# NEURON_EASYEDA.net
KiCad netlist of a schematic drawn in EasyEDA
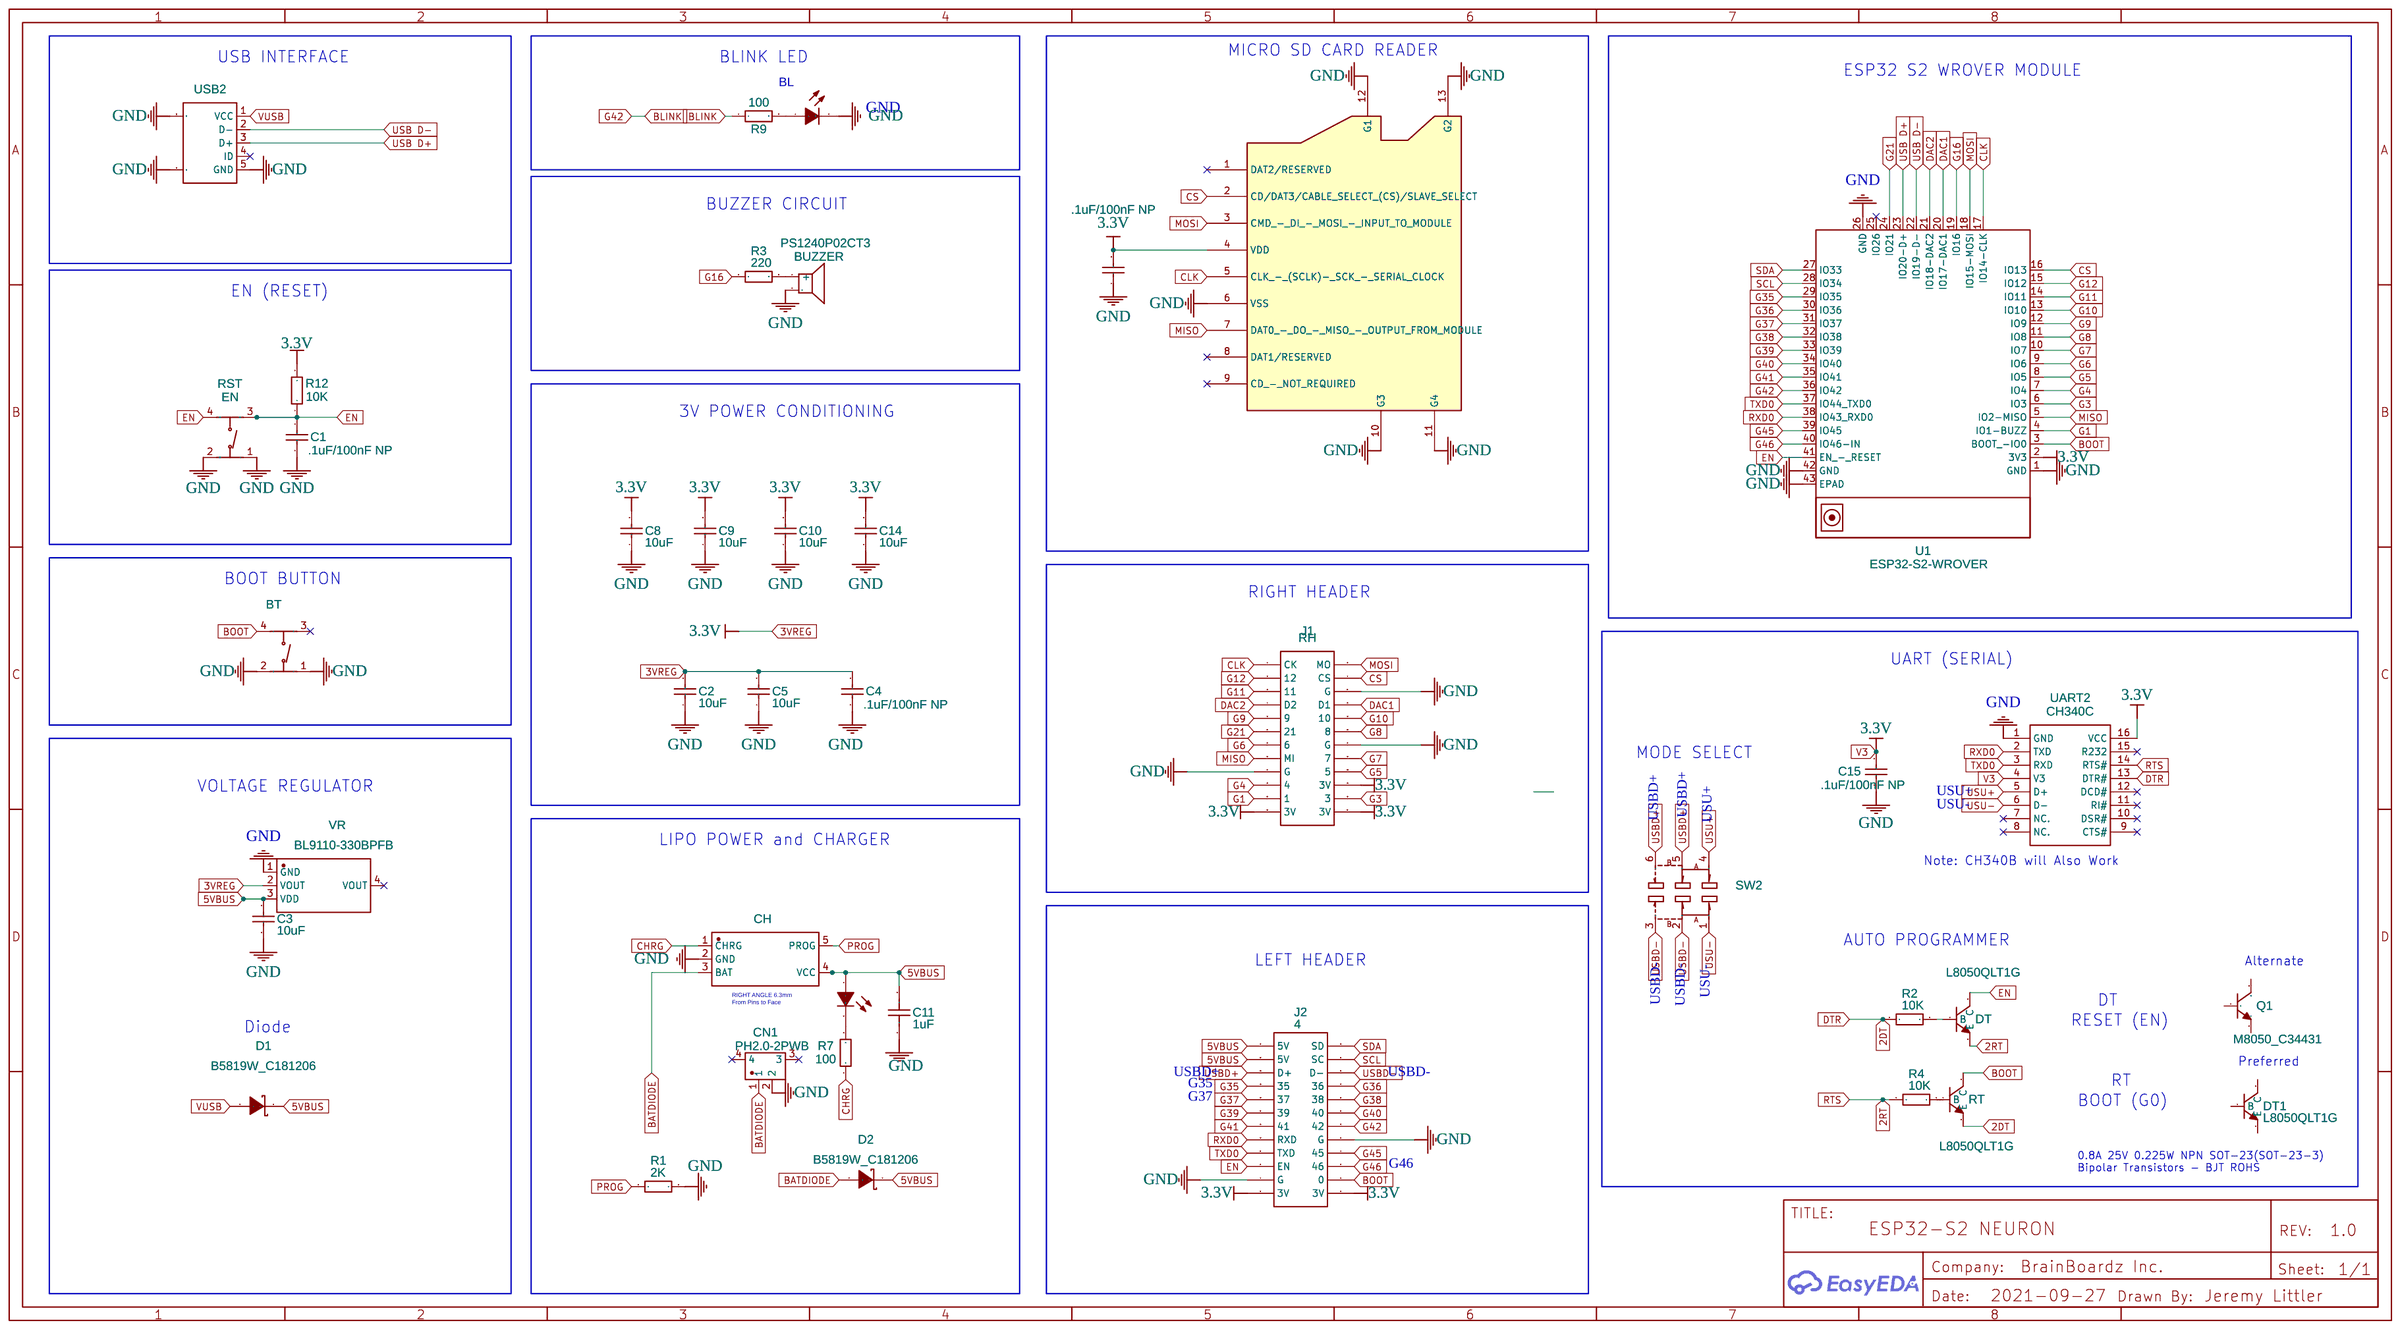
[diagram p0: schematic sheet]

(export (version "E")
  (design (tool "Eeschema 10.0.6"))
  (components
    (comp (ref "BLINK")
      (value "15-21SYGC/S530-E2/TR8")
      (fields (field (name "BOM_Supplier Part") "C73550"))
      (libsource (lib "") (part "15-21SYGC/S530-E2/TR8_1"))
    )
    (comp (ref "BT")
      (value "BOOT")
      (fields
        (field (name "BOM_Manufacturer Part") "TS-1187A-C-E-B")
        (field (name "BOM_Supplier Part") "C318887")
      )
      (libsource (lib "") (part "TS-1187A-C-E-B"))
    )
    (comp (ref "BUZZER")
      (value "PS1240P02CT3")
      (fields (field (name "BOM_Supplier Part") "C76873"))
      (libsource (lib "") (part "PS1240P02CT3"))
    )
    (comp (ref "C1")
      (value ".1uF/100nF NP")
      (fields
        (field (name "BOM_Manufacturer Part") "CL31B104KBCNNNC")
        (field (name "BOM_Supplier Part") "C24497")
      )
      (libsource (lib "") (part "CL31B104KBCNNNC_1"))
    )
    (comp (ref "C2")
      (value "10uF")
      (fields
        (field (name "BOM_Manufacturer Part") "CL31A106KBHNNNE")
        (field (name "BOM_Supplier Part") "C13585")
      )
      (libsource (lib "") (part "CL31A106KBHNNNE"))
    )
    (comp (ref "C3")
      (value "10uF")
      (fields
        (field (name "BOM_Manufacturer Part") "CL31A106KBHNNNE")
        (field (name "BOM_Supplier Part") "C13585")
      )
      (libsource (lib "") (part "CL31A106KBHNNNE"))
    )
    (comp (ref "C4")
      (value ".1uF/100nF NP")
      (fields
        (field (name "BOM_Manufacturer Part") "CL31B104KBCNNNC")
        (field (name "BOM_Supplier Part") "C24497")
      )
      (libsource (lib "") (part "CL31B104KBCNNNC_1"))
    )
    (comp (ref "C5")
      (value "10uF")
      (fields
        (field (name "BOM_Manufacturer Part") "CL31A106KBHNNNE")
        (field (name "BOM_Supplier Part") "C13585")
      )
      (libsource (lib "") (part "CL31A106KBHNNNE"))
    )
    (comp (ref "C8")
      (value "10uF")
      (fields
        (field (name "BOM_Manufacturer Part") "CL31A106KBHNNNE")
        (field (name "BOM_Supplier Part") "C13585")
      )
      (libsource (lib "") (part "CL31A106KBHNNNE"))
    )
    (comp (ref "C9")
      (value "10uF")
      (fields
        (field (name "BOM_Manufacturer Part") "CL31A106KBHNNNE")
        (field (name "BOM_Supplier Part") "C13585")
      )
      (libsource (lib "") (part "CL31A106KBHNNNE"))
    )
    (comp (ref "C10")
      (value "10uF")
      (fields
        (field (name "BOM_Manufacturer Part") "CL31A106KBHNNNE")
        (field (name "BOM_Supplier Part") "C13585")
      )
      (libsource (lib "") (part "CL31A106KBHNNNE"))
    )
    (comp (ref "C11")
      (value "1uF")
      (fields
        (field (name "BOM_Manufacturer Part") "CL31B105KBHNNNE")
        (field (name "BOM_Supplier Part") "C1848")
      )
      (libsource (lib "") (part "CL31B105KBHNNNE"))
    )
    (comp (ref "C13")
      (value ".1uF/100nF NP")
      (fields
        (field (name "BOM_Manufacturer Part") "CL31B104KBCNNNC")
        (field (name "BOM_Supplier Part") "C24497")
      )
      (libsource (lib "") (part "CL31B104KBCNNNC"))
    )
    (comp (ref "C14")
      (value "10uF")
      (fields
        (field (name "BOM_Manufacturer Part") "CL31A106KBHNNNE")
        (field (name "BOM_Supplier Part") "C13585")
      )
      (libsource (lib "") (part "CL31A106KBHNNNE"))
    )
    (comp (ref "C15")
      (value ".1uF/100nF NP")
      (fields
        (field (name "BOM_Manufacturer Part") "CL31B104KBCNNNC")
        (field (name "BOM_Supplier Part") "C24497")
      )
      (libsource (lib "") (part "CL31B104KBCNNNC"))
    )
    (comp (ref "CG")
      (value "15-21SYGC/S530-E2/TR8")
      (fields (field (name "BOM_Supplier Part") "C73550"))
      (libsource (lib "") (part "15-21SYGC/S530-E2/TR8"))
    )
    (comp (ref "CH")
      (value "CH")
      (fields (field (name "BOM_Manufacturer Part") "TP4054") (field (name "BOM_Supplier Part") "C32574"))
      (libsource (lib "") (part "TP4054"))
    )
    (comp (ref "CN1")
      (value "PH2.0-2PWB")
      (fields
        (field (name "BOM_Manufacturer Part") "PH2.0-2PWB Horizontal")
        (field (name "BOM_Supplier Part") "C47647")
      )
      (libsource (lib "") (part "PH2.0-2PWB"))
    )
    (comp (ref "D1")
      (value "B5819W_C181206")
      (fields (field (name "BOM_Manufacturer Part") "B5819W") (field (name "BOM_Supplier Part") "C181206"))
      (libsource (lib "") (part "B5819W_C181206"))
    )
    (comp (ref "D2")
      (value "B5819W_C181206")
      (fields (field (name "BOM_Manufacturer Part") "B5819W") (field (name "BOM_Supplier Part") "C181206"))
      (libsource (lib "") (part "B5819W_C181206"))
    )
    (comp (ref "DT")
      (value "L8050QLT1G")
      (fields (field (name "BOM_Supplier Part") "C49581"))
      (libsource (lib "") (part "L8050QLT1G"))
    )
    (comp (ref "DT1")
      (value "L8050QLT1G")
      (fields (field (name "BOM_Supplier Part") "C49581"))
      (libsource (lib "") (part "L8050QLT1G"))
    )
    (comp (ref "J1")
      (value "RH")
      (fields (field (name "BOM_Manufacturer Part") "New SchematicLib"))
      (libsource (lib "") (part "HDR 2.54mm 2x12_1"))
    )
    (comp (ref "J2")
      (value "4")
      (fields (field (name "BOM_Manufacturer Part") "New SchematicLib"))
      (libsource (lib "") (part "HDR 2.54mm 2x12"))
    )
    (comp (ref "MICROSD")
      (value "TF-15×15")
      (fields (field (name "BOM_Supplier Part") "C111196"))
      (libsource (lib "") (part "TF-15×15"))
    )
    (comp (ref "Q1")
      (value "M8050_C34431")
      (fields (field (name "BOM_Manufacturer Part") "M8050") (field (name "BOM_Supplier Part") "C34431"))
      (libsource (lib "") (part "M8050_C34431"))
    )
    (comp (ref "R1")
      (value "2K")
      (fields
        (field (name "BOM_Manufacturer Part") "1206W4F2001T5E")
        (field (name "BOM_Supplier Part") "C17944")
      )
      (libsource (lib "") (part "1206W4F2001T5E"))
    )
    (comp (ref "R2")
      (value "10K")
      (fields
        (field (name "BOM_Manufacturer Part") "AECR1206F10K0K9")
        (field (name "BOM_Supplier Part") "C328409")
      )
      (libsource (lib "") (part "AECR1206F10K0K9_1"))
    )
    (comp (ref "R3")
      (value "220")
      (fields
        (field (name "BOM_Manufacturer Part") "1206W4J0221T5E")
        (field (name "BOM_Supplier Part") "C25363")
      )
      (libsource (lib "") (part "1206W4J0221T5E"))
    )
    (comp (ref "R4")
      (value "10K")
      (fields
        (field (name "BOM_Manufacturer Part") "AECR1206F10K0K9")
        (field (name "BOM_Supplier Part") "C328409")
      )
      (libsource (lib "") (part "AECR1206F10K0K9_1"))
    )
    (comp (ref "R7")
      (value "100")
      (fields
        (field (name "BOM_Manufacturer Part") "1206W4F1000T5E")
        (field (name "BOM_Supplier Part") "C17901")
      )
      (libsource (lib "") (part "1206W4F1000T5E"))
    )
    (comp (ref "R9")
      (value "100")
      (fields
        (field (name "BOM_Manufacturer Part") "1206W4F1000T5E")
        (field (name "BOM_Supplier Part") "C17901")
      )
      (libsource (lib "") (part "1206W4F1000T5E_1"))
    )
    (comp (ref "R12")
      (value "10K")
      (fields
        (field (name "BOM_Manufacturer Part") "AECR1206F10K0K9")
        (field (name "BOM_Supplier Part") "C328409")
      )
      (libsource (lib "") (part "AECR1206F10K0K9"))
    )
    (comp (ref "RST")
      (value "EN")
      (fields
        (field (name "BOM_Manufacturer Part") "TS-1187A-C-E-B")
        (field (name "BOM_Supplier Part") "C318887")
      )
      (libsource (lib "") (part "TS-1187A-C-E-B_1"))
    )
    (comp (ref "RT")
      (value "L8050QLT1G")
      (fields (field (name "BOM_Supplier Part") "C49581"))
      (libsource (lib "") (part "L8050QLT1G_1"))
    )
    (comp (ref "SW2")
      (value "K2-2235D-F1")
      (fields (field (name "BOM_Supplier Part") "C108742"))
      (libsource (lib "") (part "K2-2235D-F1"))
    )
    (comp (ref "U1")
      (value "ESP32-S2-WROVER")
      (fields (field (name "BOM_Manufacturer Part") "ESP32-S2-WROVER-I"))
      (libsource (lib "") (part "ESP32-S2-WROVER-I"))
    )
    (comp (ref "UART2")
      (value "CH340C")
      (fields (field (name "BOM_Supplier Part") "C84681"))
      (libsource (lib "") (part "CH340C"))
    )
    (comp (ref "USB2")
      (value "Mini USB-B 5P-Female-TH_C46398")
      (fields
        (field (name "BOM_Manufacturer Part") "MINI 5PFemale90Degree plate four feet copper shell LCPVinyl")
        (field (name "BOM_Supplier Part") "C46398")
      )
      (libsource (lib "") (part "Mini USB-B 5P-Female-TH_C46398"))
    )
    (comp (ref "VR")
      (value "BL9110-330BPFB")
      (fields (field (name "BOM_Supplier Part") "C169246"))
      (libsource (lib "") (part "BL9110-330BPFB"))
    )
  )
  (nets
    (net (code "1") (name "2DT") (class "Default")
      (node (ref "R2") (pin "2") (pinfunction "2_2") (pintype "unspecified"))
      (node (ref "RT") (pin "2") (pinfunction "E_2") (pintype "unspecified"))
      (node (ref "UART2") (pin "13") (pinfunction "DTR#_13") (pintype "unspecified"))
    )
    (net (code "2") (name "2RT") (class "Default")
      (node (ref "DT") (pin "2") (pinfunction "E_2") (pintype "unspecified"))
      (node (ref "R4") (pin "2") (pinfunction "2_2") (pintype "unspecified"))
      (node (ref "UART2") (pin "14") (pinfunction "RTS#_14") (pintype "unspecified"))
    )
    (net (code "3") (name "3VREG") (class "Default")
      (node (ref "C10") (pin "2") (pinfunction "2_2") (pintype "input"))
      (node (ref "C13") (pin "2") (pinfunction "2_2") (pintype "input"))
      (node (ref "C14") (pin "2") (pinfunction "2_2") (pintype "input"))
      (node (ref "C15") (pin "2") (pinfunction "2_2") (pintype "input"))
      (node (ref "C2") (pin "2") (pinfunction "2_2") (pintype "input"))
      (node (ref "C4") (pin "1") (pinfunction "1_1") (pintype "input"))
      (node (ref "C5") (pin "2") (pinfunction "2_2") (pintype "input"))
      (node (ref "C8") (pin "2") (pinfunction "2_2") (pintype "input"))
      (node (ref "C9") (pin "2") (pinfunction "2_2") (pintype "input"))
      (node (ref "J1") (pin "20") (pinfunction "3V_20") (pintype "unspecified"))
      (node (ref "J1") (pin "23") (pinfunction "3V_23") (pintype "unspecified"))
      (node (ref "J1") (pin "24") (pinfunction "3V_24") (pintype "unspecified"))
      (node (ref "J2") (pin "1") (pinfunction "3V_1") (pintype "unspecified"))
      (node (ref "J2") (pin "2") (pinfunction "3V_2") (pintype "unspecified"))
      (node (ref "MICROSD") (pin "4") (pinfunction "VDD_4") (pintype "input"))
      (node (ref "R12") (pin "2") (pinfunction "2_2") (pintype "unspecified"))
      (node (ref "U1") (pin "2") (pinfunction "3V3_2") (pintype "unspecified"))
      (node (ref "UART2") (pin "16") (pinfunction "VCC_16") (pintype "unspecified"))
      (node (ref "UART2") (pin "4") (pinfunction "V3_4") (pintype "unspecified"))
      (node (ref "VR") (pin "2") (pinfunction "VOUT_2") (pintype "unspecified"))
    )
    (net (code "4") (name "5VBUS") (class "Default")
      (node (ref "C11") (pin "2") (pinfunction "2_2") (pintype "unspecified"))
      (node (ref "C3") (pin "2") (pinfunction "2_2") (pintype "input"))
      (node (ref "CG") (pin "1") (pinfunction "A_1") (pintype "input"))
      (node (ref "CH") (pin "4") (pinfunction "VCC_4") (pintype "unspecified"))
      (node (ref "D1") (pin "1") (pinfunction "K_1") (pintype "unspecified"))
      (node (ref "D2") (pin "1") (pinfunction "K_1") (pintype "unspecified"))
      (node (ref "J2") (pin "22") (pinfunction "5V_22") (pintype "unspecified"))
      (node (ref "J2") (pin "24") (pinfunction "5V_24") (pintype "unspecified"))
      (node (ref "VR") (pin "3") (pinfunction "VDD_3") (pintype "unspecified"))
    )
    (net (code "5") (name "BATDIODE") (class "Default")
      (node (ref "CH") (pin "3") (pinfunction "BAT_3") (pintype "unspecified"))
      (node (ref "CN1") (pin "1") (pinfunction "1_1") (pintype "unspecified"))
      (node (ref "D2") (pin "2") (pinfunction "A_2") (pintype "unspecified"))
    )
    (net (code "6") (name "BLINK") (class "Default")
      (node (ref "J2") (pin "11") (pinfunction "42_11") (pintype "unspecified"))
      (node (ref "R9") (pin "1") (pinfunction "1_1") (pintype "input"))
      (node (ref "U1") (pin "36") (pinfunction "IO42_36") (pintype "unspecified"))
    )
    (net (code "7") (name "BOOT") (class "Default")
      (node (ref "BT") (pin "4") (pinfunction "D_4") (pintype "unspecified"))
      (node (ref "J2") (pin "3") (pinfunction "0_3") (pintype "unspecified"))
      (node (ref "RT") (pin "3") (pinfunction "C_3") (pintype "unspecified"))
      (node (ref "U1") (pin "3") (pinfunction "BOOT_-IO0_3") (pintype "unspecified"))
    )
    (net (code "8") (name "CHRG") (class "Default")
      (node (ref "CH") (pin "1") (pinfunction "CHRG_1") (pintype "unspecified"))
      (node (ref "R7") (pin "1") (pinfunction "1_1") (pintype "input"))
    )
    (net (code "9") (name "CLK") (class "Default")
      (node (ref "J1") (pin "1") (pinfunction "CK_1") (pintype "unspecified"))
      (node (ref "MICROSD") (pin "5") (pinfunction "CLK_-_(SCLK)-_SCK_-_SERIAL_CLOCK_5") (pintype "input"))
      (node (ref "U1") (pin "17") (pinfunction "IO14-CLK_17") (pintype "unspecified"))
    )
    (net (code "10") (name "CS") (class "Default")
      (node (ref "J1") (pin "4") (pinfunction "CS_4") (pintype "unspecified"))
      (node (ref "MICROSD") (pin "2") (pinfunction "CD/DAT3/CABLE_SELECT_(CS)/SLAVE_SELECT_2") (pintype "input"))
      (node (ref "U1") (pin "16") (pinfunction "IO13_16") (pintype "unspecified"))
    )
    (net (code "11") (name "DAC1") (class "Default")
      (node (ref "J1") (pin "8") (pinfunction "D1_8") (pintype "unspecified"))
      (node (ref "U1") (pin "20") (pinfunction "IO17-DAC1_20") (pintype "unspecified"))
    )
    (net (code "12") (name "DAC2") (class "Default")
      (node (ref "J1") (pin "7") (pinfunction "D2_7") (pintype "unspecified"))
      (node (ref "U1") (pin "21") (pinfunction "IO18-DAC2_21") (pintype "unspecified"))
    )
    (net (code "13") (name "EN") (class "Default")
      (node (ref "C1") (pin "1") (pinfunction "1_1") (pintype "input"))
      (node (ref "DT") (pin "3") (pinfunction "C_3") (pintype "unspecified"))
      (node (ref "J2") (pin "6") (pinfunction "EN_6") (pintype "unspecified"))
      (node (ref "R12") (pin "1") (pinfunction "1_1") (pintype "unspecified"))
      (node (ref "RST") (pin "3") (pinfunction "C_3") (pintype "unspecified"))
      (node (ref "RST") (pin "4") (pinfunction "D_4") (pintype "unspecified"))
      (node (ref "U1") (pin "41") (pinfunction "EN_-_RESET_41") (pintype "unspecified"))
    )
    (net (code "14") (name "G1") (class "Default")
      (node (ref "J1") (pin "21") (pinfunction "1_21") (pintype "unspecified"))
      (node (ref "U1") (pin "4") (pinfunction "IO1-BUZZ_4") (pintype "unspecified"))
    )
    (net (code "15") (name "G3") (class "Default")
      (node (ref "J1") (pin "22") (pinfunction "3_22") (pintype "unspecified"))
      (node (ref "U1") (pin "6") (pinfunction "IO3_6") (pintype "unspecified"))
    )
    (net (code "16") (name "G4") (class "Default")
      (node (ref "J1") (pin "19") (pinfunction "4_19") (pintype "unspecified"))
      (node (ref "U1") (pin "7") (pinfunction "IO4_7") (pintype "unspecified"))
    )
    (net (code "17") (name "G5") (class "Default")
      (node (ref "J1") (pin "18") (pinfunction "5_18") (pintype "unspecified"))
      (node (ref "U1") (pin "8") (pinfunction "IO5_8") (pintype "unspecified"))
    )
    (net (code "18") (name "G6") (class "Default")
      (node (ref "J1") (pin "13") (pinfunction "6_13") (pintype "unspecified"))
      (node (ref "U1") (pin "9") (pinfunction "IO6_9") (pintype "unspecified"))
    )
    (net (code "19") (name "G7") (class "Default")
      (node (ref "J1") (pin "16") (pinfunction "7_16") (pintype "unspecified"))
      (node (ref "U1") (pin "10") (pinfunction "IO7_10") (pintype "unspecified"))
    )
    (net (code "20") (name "G8") (class "Default")
      (node (ref "J1") (pin "12") (pinfunction "8_12") (pintype "unspecified"))
      (node (ref "U1") (pin "11") (pinfunction "IO8_11") (pintype "unspecified"))
    )
    (net (code "21") (name "G9") (class "Default")
      (node (ref "J1") (pin "9") (pinfunction "9_9") (pintype "unspecified"))
      (node (ref "U1") (pin "12") (pinfunction "IO9_12") (pintype "unspecified"))
    )
    (net (code "22") (name "G10") (class "Default")
      (node (ref "J1") (pin "10") (pinfunction "10_10") (pintype "unspecified"))
      (node (ref "U1") (pin "13") (pinfunction "IO10_13") (pintype "unspecified"))
    )
    (net (code "23") (name "G11") (class "Default")
      (node (ref "J1") (pin "5") (pinfunction "11_5") (pintype "unspecified"))
      (node (ref "U1") (pin "14") (pinfunction "IO11_14") (pintype "unspecified"))
    )
    (net (code "24") (name "G12") (class "Default")
      (node (ref "J1") (pin "3") (pinfunction "12_3") (pintype "unspecified"))
      (node (ref "U1") (pin "15") (pinfunction "IO12_15") (pintype "unspecified"))
    )
    (net (code "25") (name "G16") (class "Default")
      (node (ref "R3") (pin "1") (pinfunction "1_1") (pintype "input"))
      (node (ref "U1") (pin "19") (pinfunction "IO16_19") (pintype "unspecified"))
    )
    (net (code "26") (name "G21") (class "Default")
      (node (ref "J1") (pin "11") (pinfunction "21_11") (pintype "unspecified"))
      (node (ref "U1") (pin "24") (pinfunction "IO21_24") (pintype "unspecified"))
    )
    (net (code "27") (name "G35") (class "Default")
      (node (ref "J2") (pin "18") (pinfunction "35_18") (pintype "unspecified"))
      (node (ref "U1") (pin "29") (pinfunction "IO35_29") (pintype "unspecified"))
    )
    (net (code "28") (name "G36") (class "Default")
      (node (ref "J2") (pin "17") (pinfunction "36_17") (pintype "unspecified"))
      (node (ref "U1") (pin "30") (pinfunction "IO36_30") (pintype "unspecified"))
    )
    (net (code "29") (name "G37") (class "Default")
      (node (ref "J2") (pin "16") (pinfunction "37_16") (pintype "unspecified"))
      (node (ref "U1") (pin "31") (pinfunction "IO37_31") (pintype "unspecified"))
    )
    (net (code "30") (name "G38") (class "Default")
      (node (ref "J2") (pin "15") (pinfunction "38_15") (pintype "unspecified"))
      (node (ref "U1") (pin "32") (pinfunction "IO38_32") (pintype "unspecified"))
    )
    (net (code "31") (name "G39") (class "Default")
      (node (ref "J2") (pin "14") (pinfunction "39_14") (pintype "unspecified"))
      (node (ref "U1") (pin "33") (pinfunction "IO39_33") (pintype "unspecified"))
    )
    (net (code "32") (name "G40") (class "Default")
      (node (ref "J2") (pin "13") (pinfunction "40_13") (pintype "unspecified"))
      (node (ref "U1") (pin "34") (pinfunction "IO40_34") (pintype "unspecified"))
    )
    (net (code "33") (name "G41") (class "Default")
      (node (ref "J2") (pin "12") (pinfunction "41_12") (pintype "unspecified"))
      (node (ref "U1") (pin "35") (pinfunction "IO41_35") (pintype "unspecified"))
    )
    (net (code "34") (name "G45") (class "Default")
      (node (ref "J2") (pin "7") (pinfunction "45_7") (pintype "unspecified"))
      (node (ref "U1") (pin "39") (pinfunction "IO45_39") (pintype "unspecified"))
    )
    (net (code "35") (name "G46") (class "Default")
      (node (ref "J2") (pin "5") (pinfunction "46_5") (pintype "unspecified"))
      (node (ref "U1") (pin "40") (pinfunction "IO46-IN_40") (pintype "unspecified"))
    )
    (net (code "36") (name "GND") (class "Default")
      (node (ref "BLINK") (pin "2") (pinfunction "C_2") (pintype "input"))
      (node (ref "BT") (pin "1") (pinfunction "A_1") (pintype "unspecified"))
      (node (ref "BT") (pin "2") (pinfunction "B_2") (pintype "unspecified"))
      (node (ref "BUZZER") (pin "2") (pinfunction "2_2") (pintype "unspecified"))
      (node (ref "C1") (pin "2") (pinfunction "2_2") (pintype "input"))
      (node (ref "C10") (pin "1") (pinfunction "1_1") (pintype "input"))
      (node (ref "C11") (pin "1") (pinfunction "1_1") (pintype "unspecified"))
      (node (ref "C13") (pin "1") (pinfunction "1_1") (pintype "input"))
      (node (ref "C14") (pin "1") (pinfunction "1_1") (pintype "input"))
      (node (ref "C15") (pin "1") (pinfunction "1_1") (pintype "input"))
      (node (ref "C2") (pin "1") (pinfunction "1_1") (pintype "input"))
      (node (ref "C3") (pin "1") (pinfunction "1_1") (pintype "input"))
      (node (ref "C4") (pin "2") (pinfunction "2_2") (pintype "input"))
      (node (ref "C5") (pin "1") (pinfunction "1_1") (pintype "input"))
      (node (ref "C8") (pin "1") (pinfunction "1_1") (pintype "input"))
      (node (ref "C9") (pin "1") (pinfunction "1_1") (pintype "input"))
      (node (ref "CH") (pin "2") (pinfunction "GND_2") (pintype "unspecified"))
      (node (ref "CN1") (pin "2") (pinfunction "2_2") (pintype "unspecified"))
      (node (ref "J1") (pin "14") (pinfunction "G_14") (pintype "unspecified"))
      (node (ref "J1") (pin "17") (pinfunction "G_17") (pintype "unspecified"))
      (node (ref "J1") (pin "6") (pinfunction "G_6") (pintype "unspecified"))
      (node (ref "J2") (pin "4") (pinfunction "G_4") (pintype "unspecified"))
      (node (ref "J2") (pin "9") (pinfunction "G_9") (pintype "unspecified"))
      (node (ref "MICROSD") (pin "10") (pinfunction "G3_10") (pintype "input"))
      (node (ref "MICROSD") (pin "11") (pinfunction "G4_11") (pintype "input"))
      (node (ref "MICROSD") (pin "12") (pinfunction "G1_12") (pintype "input"))
      (node (ref "MICROSD") (pin "13") (pinfunction "G2_13") (pintype "input"))
      (node (ref "MICROSD") (pin "6") (pinfunction "VSS_6") (pintype "input"))
      (node (ref "R1") (pin "2") (pinfunction "2_2") (pintype "input"))
      (node (ref "RST") (pin "1") (pinfunction "A_1") (pintype "unspecified"))
      (node (ref "RST") (pin "2") (pinfunction "B_2") (pintype "unspecified"))
      (node (ref "U1") (pin "1") (pinfunction "GND_1") (pintype "unspecified"))
      (node (ref "U1") (pin "26") (pinfunction "GND_26") (pintype "unspecified"))
      (node (ref "U1") (pin "42") (pinfunction "GND_42") (pintype "unspecified"))
      (node (ref "U1") (pin "43") (pinfunction "EPAD_43") (pintype "unspecified"))
      (node (ref "UART2") (pin "1") (pinfunction "GND_1") (pintype "unspecified"))
      (node (ref "USB2") (pin "0") (pinfunction "0_0") (pintype "unspecified"))
      (node (ref "USB2") (pin "5") (pinfunction "GND_5") (pintype "input"))
      (node (ref "VR") (pin "1") (pinfunction "GND_1") (pintype "unspecified"))
    )
    (net (code "37") (name "MISO") (class "Default")
      (node (ref "J1") (pin "15") (pinfunction "MI_15") (pintype "unspecified"))
      (node (ref "MICROSD") (pin "7") (pinfunction "DAT0_-_DO_-_MISO_-_OUTPUT_FROM_MODULE_7") (pintype "input"))
      (node (ref "U1") (pin "5") (pinfunction "IO2-MISO_5") (pintype "unspecified"))
    )
    (net (code "38") (name "MOSI") (class "Default")
      (node (ref "J1") (pin "2") (pinfunction "MO_2") (pintype "unspecified"))
      (node (ref "MICROSD") (pin "3") (pinfunction "CMD_-_DI_-_MOSI_-_INPUT_TO_MODULE_3") (pintype "input"))
      (node (ref "U1") (pin "18") (pinfunction "IO15-MOSI_18") (pintype "unspecified"))
    )
    (net (code "39") (name "Net-(BLINK-A)") (class "Default")
      (node (ref "BLINK") (pin "1") (pinfunction "A_1") (pintype "input"))
      (node (ref "R9") (pin "2") (pinfunction "2_2") (pintype "input"))
    )
    (net (code "40") (name "Net-(BUZZER-+)") (class "Default")
      (node (ref "BUZZER") (pin "1") (pinfunction "+_1") (pintype "unspecified"))
      (node (ref "R3") (pin "2") (pinfunction "2_2") (pintype "input"))
    )
    (net (code "41") (name "Net-(CG-C)") (class "Default")
      (node (ref "CG") (pin "2") (pinfunction "C_2") (pintype "input"))
      (node (ref "R7") (pin "2") (pinfunction "2_2") (pintype "input"))
    )
    (net (code "42") (name "Net-(DT-B)") (class "Default")
      (node (ref "DT") (pin "1") (pinfunction "B_1") (pintype "unspecified"))
      (node (ref "R2") (pin "1") (pinfunction "1_1") (pintype "unspecified"))
    )
    (net (code "43") (name "PROG") (class "Default")
      (node (ref "CH") (pin "5") (pinfunction "PROG_5") (pintype "unspecified"))
      (node (ref "R1") (pin "1") (pinfunction "1_1") (pintype "input"))
    )
    (net (code "44") (name "RXD0") (class "Default")
      (node (ref "J2") (pin "10") (pinfunction "RXD_10") (pintype "unspecified"))
      (node (ref "U1") (pin "38") (pinfunction "IO43_RXD0_38") (pintype "unspecified"))
      (node (ref "UART2") (pin "2") (pinfunction "TXD_2") (pintype "unspecified"))
    )
    (net (code "45") (name "SCL") (class "Default")
      (node (ref "J2") (pin "21") (pinfunction "SC_21") (pintype "unspecified"))
      (node (ref "U1") (pin "28") (pinfunction "IO34_28") (pintype "unspecified"))
    )
    (net (code "46") (name "SDA") (class "Default")
      (node (ref "J2") (pin "23") (pinfunction "SD_23") (pintype "unspecified"))
      (node (ref "U1") (pin "27") (pinfunction "IO33_27") (pintype "unspecified"))
    )
    (net (code "47") (name "TXD0") (class "Default")
      (node (ref "J2") (pin "8") (pinfunction "TXD_8") (pintype "unspecified"))
      (node (ref "U1") (pin "37") (pinfunction "IO44_TXD0_37") (pintype "unspecified"))
      (node (ref "UART2") (pin "3") (pinfunction "RXD_3") (pintype "unspecified"))
    )
    (net (code "48") (name "USB D+") (class "Default")
      (node (ref "U1") (pin "23") (pinfunction "IO20-D+_23") (pintype "unspecified"))
      (node (ref "USB2") (pin "3") (pinfunction "D+_3") (pintype "input"))
    )
    (net (code "49") (name "USB D-") (class "Default")
      (node (ref "U1") (pin "22") (pinfunction "IO19-D-_22") (pintype "unspecified"))
      (node (ref "USB2") (pin "2") (pinfunction "D-_2") (pintype "input"))
    )
    (net (code "50") (name "USBD+") (class "Default")
      (node (ref "J2") (pin "20") (pinfunction "D+_20") (pintype "unspecified"))
      (node (ref "SW2") (pin "5") (pinfunction "5_5") (pintype "unspecified"))
      (node (ref "SW2") (pin "6") (pinfunction "6_6") (pintype "unspecified"))
    )
    (net (code "51") (name "USBD-") (class "Default")
      (node (ref "J2") (pin "19") (pinfunction "D-_19") (pintype "unspecified"))
      (node (ref "SW2") (pin "2") (pinfunction "2_2") (pintype "unspecified"))
      (node (ref "SW2") (pin "3") (pinfunction "3_3") (pintype "unspecified"))
    )
    (net (code "52") (name "USU+") (class "Default")
      (node (ref "SW2") (pin "4") (pinfunction "4_4") (pintype "unspecified"))
      (node (ref "UART2") (pin "5") (pinfunction "D+_5") (pintype "unspecified"))
    )
    (net (code "53") (name "USU-") (class "Default")
      (node (ref "SW2") (pin "1") (pinfunction "1_1") (pintype "unspecified"))
      (node (ref "UART2") (pin "6") (pinfunction "D-_6") (pintype "unspecified"))
    )
    (net (code "54") (name "VUSB") (class "Default")
      (node (ref "D1") (pin "2") (pinfunction "A_2") (pintype "unspecified"))
      (node (ref "USB2") (pin "1") (pinfunction "VCC_1") (pintype "input"))
    )
    (net (code "55") (name "unconnected-(BT-C-Pad3)") (class "Default")
      (node (ref "BT") (pin "3") (pinfunction "C_3") (pintype "unspecified+no_connect"))
    )
    (net (code "56") (name "unconnected-(CN1-Pad3)") (class "Default")
      (node (ref "CN1") (pin "3") (pinfunction "3_3") (pintype "unspecified+no_connect"))
    )
    (net (code "57") (name "unconnected-(CN1-Pad4)") (class "Default")
      (node (ref "CN1") (pin "4") (pinfunction "4_4") (pintype "unspecified+no_connect"))
    )
    (net (code "58") (name "unconnected-(DT1-B-Pad1)") (class "Default")
      (node (ref "DT1") (pin "1") (pinfunction "B_1") (pintype "unspecified"))
    )
    (net (code "59") (name "unconnected-(DT1-C-Pad3)") (class "Default")
      (node (ref "DT1") (pin "3") (pinfunction "C_3") (pintype "unspecified"))
    )
    (net (code "60") (name "unconnected-(DT1-E-Pad2)") (class "Default")
      (node (ref "DT1") (pin "2") (pinfunction "E_2") (pintype "unspecified"))
    )
    (net (code "61") (name "unconnected-(MICROSD-CD_-_NOT_REQUIRED-Pad9)") (class "Default")
      (node (ref "MICROSD") (pin "9") (pinfunction "CD_-_NOT_REQUIRED_9") (pintype "input+no_connect"))
    )
    (net (code "62") (name "unconnected-(MICROSD-DAT1{slash}RESERVED-Pad8)") (class "Default")
      (node (ref "MICROSD") (pin "8") (pinfunction "DAT1/RESERVED_8") (pintype "input+no_connect"))
    )
    (net (code "63") (name "unconnected-(MICROSD-DAT2{slash}RESERVED-Pad1)") (class "Default")
      (node (ref "MICROSD") (pin "1") (pinfunction "DAT2/RESERVED_1") (pintype "input+no_connect"))
    )
    (net (code "64") (name "unconnected-(Q1-B-Pad1)") (class "Default")
      (node (ref "Q1") (pin "1") (pinfunction "B_1") (pintype "unspecified"))
    )
    (net (code "65") (name "unconnected-(Q1-C-Pad3)") (class "Default")
      (node (ref "Q1") (pin "3") (pinfunction "C_3") (pintype "unspecified"))
    )
    (net (code "66") (name "unconnected-(Q1-E-Pad2)") (class "Default")
      (node (ref "Q1") (pin "2") (pinfunction "E_2") (pintype "unspecified"))
    )
    (net (code "67") (name "unconnected-(R4-Pad1)") (class "Default")
      (node (ref "R4") (pin "1") (pinfunction "1_1") (pintype "unspecified"))
    )
    (net (code "68") (name "unconnected-(RT-B-Pad1)") (class "Default")
      (node (ref "RT") (pin "1") (pinfunction "B_1") (pintype "unspecified"))
    )
    (net (code "69") (name "unconnected-(U1-IO26-Pad25)") (class "Default")
      (node (ref "U1") (pin "25") (pinfunction "IO26_25") (pintype "unspecified+no_connect"))
    )
    (net (code "70") (name "unconnected-(UART2-CTS#-Pad9)") (class "Default")
      (node (ref "UART2") (pin "9") (pinfunction "CTS#_9") (pintype "unspecified+no_connect"))
    )
    (net (code "71") (name "unconnected-(UART2-DCD#-Pad12)") (class "Default")
      (node (ref "UART2") (pin "12") (pinfunction "DCD#_12") (pintype "unspecified+no_connect"))
    )
    (net (code "72") (name "unconnected-(UART2-DSR#-Pad10)") (class "Default")
      (node (ref "UART2") (pin "10") (pinfunction "DSR#_10") (pintype "unspecified+no_connect"))
    )
    (net (code "73") (name "unconnected-(UART2-NC.-Pad7)") (class "Default")
      (node (ref "UART2") (pin "7") (pinfunction "NC._7") (pintype "unspecified+no_connect"))
    )
    (net (code "74") (name "unconnected-(UART2-NC.-Pad8)") (class "Default")
      (node (ref "UART2") (pin "8") (pinfunction "NC._8") (pintype "unspecified+no_connect"))
    )
    (net (code "75") (name "unconnected-(UART2-R232-Pad15)") (class "Default")
      (node (ref "UART2") (pin "15") (pinfunction "R232_15") (pintype "unspecified+no_connect"))
    )
    (net (code "76") (name "unconnected-(UART2-RI#-Pad11)") (class "Default")
      (node (ref "UART2") (pin "11") (pinfunction "RI#_11") (pintype "unspecified+no_connect"))
    )
    (net (code "77") (name "unconnected-(USB2-ID-Pad4)") (class "Default")
      (node (ref "USB2") (pin "4") (pinfunction "ID_4") (pintype "input+no_connect"))
    )
    (net (code "78") (name "unconnected-(VR-VOUT-Pad4)") (class "Default")
      (node (ref "VR") (pin "4") (pinfunction "VOUT_4") (pintype "unspecified+no_connect"))
    )
  )
)
